# schematic.net
KiCad netlist of a schematic drawn in Altium Designer
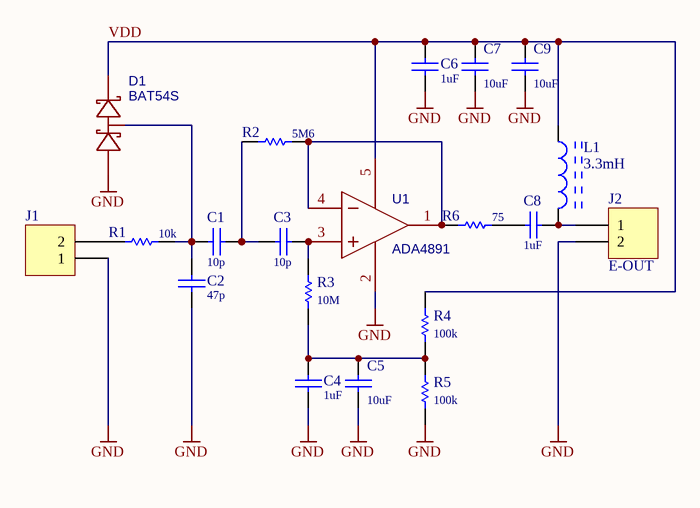
[diagram p0: schematic.SchDoc]

(export (version "E")
  (design (tool "Eeschema 10.0.6"))
  (components
    (comp (ref "C1")
      (value "10p")
      (footprint "C0603")
      (description "10pF 0603")
      (libsource (lib "Miscellaneous Devices") (part "CAP"))
    )
    (comp (ref "C2")
      (value "47p")
      (footprint "C0603")
      (description "47pF 0603")
      (libsource (lib "Miscellaneous Devices") (part "CAP"))
    )
    (comp (ref "C3")
      (value "10p")
      (footprint "C0603")
      (description "10pF 0603")
      (libsource (lib "Miscellaneous Devices") (part "CAP"))
    )
    (comp (ref "C4")
      (value "1uF")
      (footprint "C0603")
      (description "1uF 0603")
      (libsource (lib "Miscellaneous Devices") (part "CAP"))
    )
    (comp (ref "C5")
      (value "10uF")
      (footprint "C1206")
      (description "10uf 50V 1206")
      (libsource (lib "Miscellaneous Devices") (part "CAP"))
    )
    (comp (ref "C6")
      (value "1uF")
      (footprint "C0603")
      (description "1uF 0603")
      (libsource (lib "Miscellaneous Devices") (part "CAP"))
    )
    (comp (ref "C7")
      (value "10uF")
      (footprint "C1206")
      (description "10uf 50V 1206")
      (libsource (lib "Miscellaneous Devices") (part "CAP"))
    )
    (comp (ref "C8")
      (value "1uF")
      (footprint "C0603")
      (description "1uF 0603")
      (libsource (lib "Miscellaneous Devices") (part "CAP"))
    )
    (comp (ref "C9")
      (value "10uF")
      (footprint "C1206")
      (description "10uf 50V 1206")
      (libsource (lib "Miscellaneous Devices") (part "CAP"))
    )
    (comp (ref "D1")
      (value "BAT54S")
      (footprint "SOT-23")
      (libsource (lib "Schlib1") (part "BAT54S_C916425"))
    )
    (comp (ref "J1")
      (value "CONN_DG308-2.54-2P")
      (footprint "CONN_DG308-2.54-2P")
      (libsource (lib "Miscellaneous Devices") (part "CONN MOLEX HDR-M 1x4"))
    )
    (comp (ref "J2")
      (value "E-OUT")
      (footprint "CONN_F_TYPE")
      (libsource (lib "") (part "CONN MOLEX HDR-M 1x4_1"))
    )
    (comp (ref "L1")
      (value "3.3mH")
      (footprint "IND-TH_BD5.0-L10.5-P14.50-D0.6")
      (description "CKL0510*3.3mH/K-A T")
      (libsource (lib "Miscellaneous Devices") (part "SRN3015-4R7M"))
    )
    (comp (ref "R1")
      (value "10k")
      (footprint "R0603")
      (description "10k 0603")
      (libsource (lib "Miscellaneous Devices") (part "RES"))
    )
    (comp (ref "R2")
      (value "5M6")
      (footprint "R0603")
      (description "5M6 0603")
      (libsource (lib "Miscellaneous Devices") (part "RES"))
    )
    (comp (ref "R3")
      (value "10M")
      (footprint "R0603")
      (description "10M 0603")
      (libsource (lib "Miscellaneous Devices") (part "RES"))
    )
    (comp (ref "R4")
      (value "100k")
      (footprint "R0603")
      (description "100k 0603")
      (libsource (lib "Miscellaneous Devices") (part "RES"))
    )
    (comp (ref "R5")
      (value "100k")
      (footprint "R0603")
      (description "100k 0603")
      (libsource (lib "Miscellaneous Devices") (part "RES"))
    )
    (comp (ref "R6")
      (value "75")
      (footprint "R0603")
      (description "75R 0603")
      (libsource (lib "Miscellaneous Devices") (part "RES"))
    )
    (comp (ref "U1")
      (value "ADA4891")
      (footprint "SOT-23-5")
      (description "ADA4891-1ARJZ-R7")
      (libsource (lib "altium-import") (part "root_0_ADA4891-1ARJZ-R7_"))
    )
  )
  (nets
    (net (code "1") (name "/VDD") (class "Default")
      (node (ref "C6") (pin "2") (pinfunction "2_2") (pintype "passive"))
      (node (ref "C7") (pin "2") (pinfunction "2_2") (pintype "passive"))
      (node (ref "C9") (pin "2") (pinfunction "2_2") (pintype "passive"))
      (node (ref "D1") (pin "2") (pinfunction "K_2") (pintype "passive"))
      (node (ref "L1") (pin "1") (pinfunction "1_1") (pintype "passive"))
      (node (ref "R4") (pin "2") (pinfunction "2_2") (pintype "passive"))
      (node (ref "U1") (pin "5") (pinfunction "+VS_5") (pintype "passive"))
    )
    (net (code "2") (name "GND") (class "Default")
      (node (ref "C2") (pin "2") (pinfunction "2_2") (pintype "passive"))
      (node (ref "C4") (pin "1") (pinfunction "1_1") (pintype "passive"))
      (node (ref "C5") (pin "1") (pinfunction "1_1") (pintype "passive"))
      (node (ref "C6") (pin "1") (pinfunction "1_1") (pintype "passive"))
      (node (ref "C7") (pin "1") (pinfunction "1_1") (pintype "passive"))
      (node (ref "C9") (pin "1") (pinfunction "1_1") (pintype "passive"))
      (node (ref "D1") (pin "1") (pinfunction "A_1") (pintype "passive"))
      (node (ref "J1") (pin "1") (pinfunction "1_1") (pintype "passive"))
      (node (ref "J2") (pin "2") (pinfunction "2_2") (pintype "passive"))
      (node (ref "R5") (pin "1") (pinfunction "1_1") (pintype "passive"))
      (node (ref "U1") (pin "2") (pinfunction "-VS_2") (pintype "passive"))
    )
    (net (code "3") (name "Net-(C1-Pad1)") (class "Default")
      (node (ref "C1") (pin "1") (pinfunction "1_1") (pintype "passive"))
      (node (ref "C3") (pin "2") (pinfunction "2_2") (pintype "passive"))
      (node (ref "R2") (pin "1") (pinfunction "1_1") (pintype "passive"))
    )
    (net (code "4") (name "Net-(C1-Pad2)") (class "Default")
      (node (ref "C1") (pin "2") (pinfunction "2_2") (pintype "passive"))
      (node (ref "C2") (pin "1") (pinfunction "1_1") (pintype "passive"))
      (node (ref "D1") (pin "3") (pinfunction "3_3") (pintype "passive"))
      (node (ref "R1") (pin "2") (pinfunction "2_2") (pintype "passive"))
    )
    (net (code "5") (name "Net-(C4-Pad2)") (class "Default")
      (node (ref "C4") (pin "2") (pinfunction "2_2") (pintype "passive"))
      (node (ref "C5") (pin "2") (pinfunction "2_2") (pintype "passive"))
      (node (ref "R3") (pin "1") (pinfunction "1_1") (pintype "passive"))
      (node (ref "R4") (pin "1") (pinfunction "1_1") (pintype "passive"))
      (node (ref "R5") (pin "2") (pinfunction "2_2") (pintype "passive"))
    )
    (net (code "6") (name "Net-(C8-Pad1)") (class "Default")
      (node (ref "C8") (pin "1") (pinfunction "1_1") (pintype "passive"))
      (node (ref "J2") (pin "1") (pinfunction "1_1") (pintype "passive"))
      (node (ref "L1") (pin "2") (pinfunction "2_2") (pintype "passive"))
    )
    (net (code "7") (name "Net-(C8-Pad2)") (class "Default")
      (node (ref "C8") (pin "2") (pinfunction "2_2") (pintype "passive"))
      (node (ref "R6") (pin "2") (pinfunction "2_2") (pintype "passive"))
    )
    (net (code "8") (name "Net-(J1-Pad2)") (class "Default")
      (node (ref "J1") (pin "2") (pinfunction "2_2") (pintype "passive"))
      (node (ref "R1") (pin "1") (pinfunction "1_1") (pintype "passive"))
    )
    (net (code "9") (name "Net-(U1-+IN)") (class "Default")
      (node (ref "C3") (pin "1") (pinfunction "1_1") (pintype "passive"))
      (node (ref "R3") (pin "2") (pinfunction "2_2") (pintype "passive"))
      (node (ref "U1") (pin "3") (pinfunction "+IN_3") (pintype "passive"))
    )
    (net (code "10") (name "Net-(U1--IN)") (class "Default")
      (node (ref "R2") (pin "2") (pinfunction "2_2") (pintype "passive"))
      (node (ref "R6") (pin "1") (pinfunction "1_1") (pintype "passive"))
      (node (ref "U1") (pin "1") (pinfunction "OUT_1") (pintype "passive"))
      (node (ref "U1") (pin "4") (pinfunction "-IN_4") (pintype "passive"))
    )
  )
)
